# PROC099A_LC_Filtering_Reference.net
KiCad netlist of a schematic drawn in Altium Designer
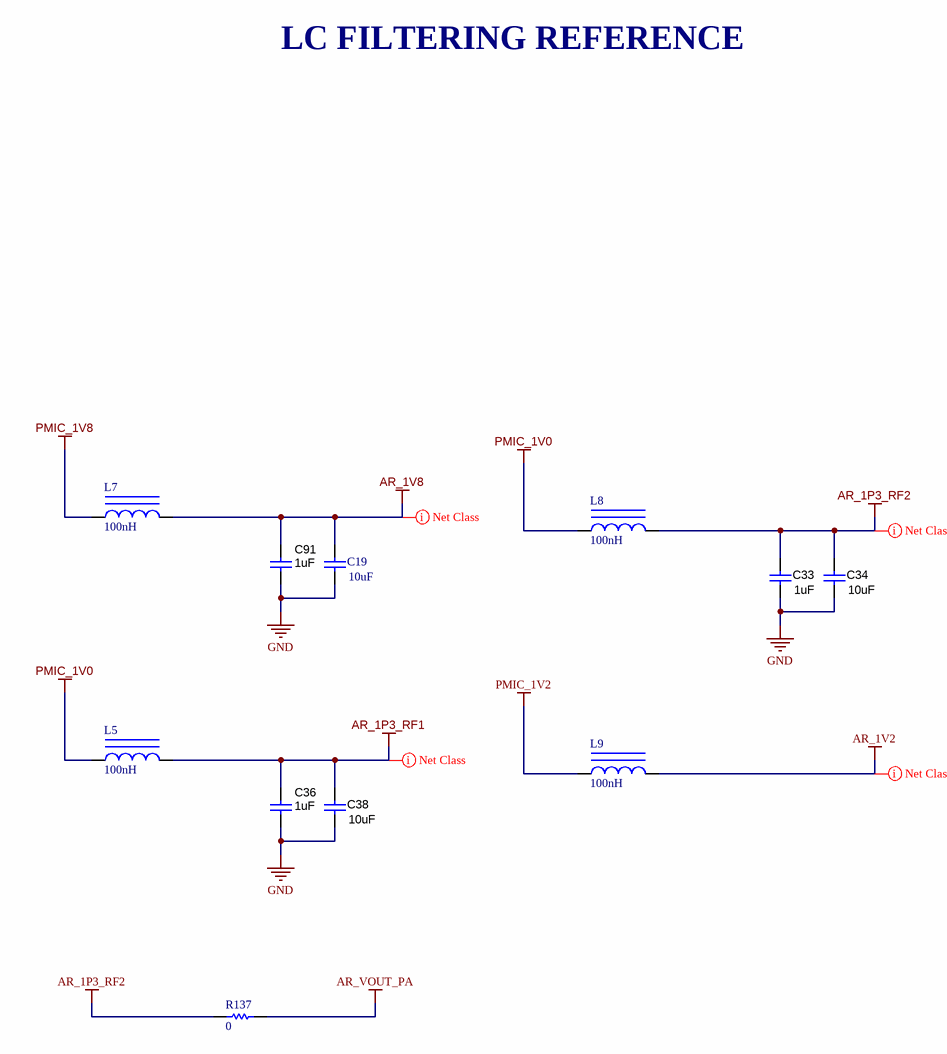
[diagram p0: PROC099A_LC_Filtering_Reference.SchDoc]

(export (version "E")
  (design (tool "Eeschema 10.0.6"))
  (components
    (comp (ref "C19")
      (value "GCM21BR71A106KE22L")
      (footprint "0805_HV")
      (description "CAP, CERM, 10 uF, 10 V, +/- 10%, X7R, 0805")
      (fields
        (field (name "MANUFACTURER") "MuRata")
        (field (name "VALUEDISPLAYED") "10uF")
        (field (name "PUBLISHER") "Texas Instruments")
      )
      (libsource (lib "Altium Vault - TI") (part "Capacitor"))
    )
    (comp (ref "C33")
      (value "GCM188R71C105KA64D")
      (footprint "0603")
      (description "CAP, CERM, 1 uF, 16 V, +/- 10%, X7R, AEC-Q200 Grade 1, 0603")
      (fields
        (field (name "MANUFACTURER") "MuRata")
        (field (name "VALUEDISPLAYED") "1uF")
        (field (name "PUBLISHER") "Texas Instruments")
      )
      (libsource (lib "Altium Vault - TI") (part "Capacitor"))
    )
    (comp (ref "C34")
      (value "GCM21BR71A106KE22L")
      (footprint "0805_HV")
      (description "CAP, CERM, 10 uF, 10 V, +/- 10%, X7R, 0805")
      (fields
        (field (name "MANUFACTURER") "MuRata")
        (field (name "VALUEDISPLAYED") "10uF")
        (field (name "PUBLISHER") "Texas Instruments")
      )
      (libsource (lib "Altium Vault - TI") (part "CMP-0008017-2"))
    )
    (comp (ref "C36")
      (value "GCM188R71C105KA64D")
      (footprint "0603")
      (description "CAP, CERM, 1 uF, 16 V, +/- 10%, X7R, AEC-Q200 Grade 1, 0603")
      (fields
        (field (name "MANUFACTURER") "MuRata")
        (field (name "VALUEDISPLAYED") "1uF")
        (field (name "PUBLISHER") "Texas Instruments")
      )
      (libsource (lib "Altium Vault - TI") (part "Capacitor"))
    )
    (comp (ref "C38")
      (value "GCM21BR71A106KE22L")
      (footprint "0805_HV")
      (description "CAP, CERM, 10 uF, 10 V, +/- 10%, X7R, 0805")
      (fields
        (field (name "MANUFACTURER") "MuRata")
        (field (name "VALUEDISPLAYED") "10uF")
        (field (name "PUBLISHER") "Texas Instruments")
      )
      (libsource (lib "Altium Vault - TI") (part "CMP-0008017-2"))
    )
    (comp (ref "C91")
      (value "GCM188R71C105KA64D")
      (footprint "0603")
      (description "CAP, CERM, 1 uF, 16 V, +/- 10%, X7R, AEC-Q200 Grade 1, 0603")
      (fields
        (field (name "MANUFACTURER") "MuRata")
        (field (name "VALUEDISPLAYED") "1uF")
        (field (name "PUBLISHER") "Texas Instruments")
      )
      (libsource (lib "Altium Vault - TI") (part "Capacitor"))
    )
    (comp (ref "L5")
      (value "NLCV32T-R10M-EFRD")
      (footprint "NLCV32")
      (description "Inductor, Wirewound, Ferrite, 100 nH, 2.85 A, 0.024 ohm, AEC-Q200 Grade 1, SMD")
      (fields (field (name "MANUFACTURER") "TDK") (field (name "VALUEDISPLAYED") "100nH"))
      (libsource (lib "Altium Vault - TI") (part "Inductor_Iron"))
    )
    (comp (ref "L7")
      (value "NLCV32T-R10M-EFRD")
      (footprint "NLCV32")
      (description "Inductor, Wirewound, Ferrite, 100 nH, 2.85 A, 0.024 ohm, AEC-Q200 Grade 1, SMD")
      (fields (field (name "MANUFACTURER") "TDK") (field (name "VALUEDISPLAYED") "100nH"))
      (libsource (lib "Altium Vault - TI") (part "Inductor_Iron"))
    )
    (comp (ref "L8")
      (value "NLCV32T-R10M-EFRD")
      (footprint "NLCV32")
      (description "Inductor, Wirewound, Ferrite, 100 nH, 2.85 A, 0.024 ohm, AEC-Q200 Grade 1, SMD")
      (fields (field (name "MANUFACTURER") "TDK") (field (name "VALUEDISPLAYED") "100nH"))
      (libsource (lib "Altium Vault - TI") (part "Inductor_Iron"))
    )
    (comp (ref "L9")
      (value "NLCV32T-R10M-EFRD")
      (footprint "NLCV32")
      (description "Inductor, Wirewound, Ferrite, 100 nH, 2.85 A, 0.024 ohm, AEC-Q200 Grade 1, SMD")
      (fields (field (name "MANUFACTURER") "TDK") (field (name "VALUEDISPLAYED") "100nH"))
      (libsource (lib "Altium Vault - TI") (part "Inductor_Iron"))
    )
    (comp (ref "R137")
      (value "MCT06030Z0000ZP500")
      (footprint "0603")
      (description "RES, 0, 5%, 0.125 W, 0603")
      (fields
        (field (name "MANUFACTURER") "Vishay/Beyschlag")
        (field (name "VALUEDISPLAYED") "0")
        (field (name "PUBLISHER") "Texas Instruments")
      )
      (libsource (lib "Altium Vault - TI") (part "CMP-0025884-3"))
    )
  )
  (nets
    (net (code "1") (name "AR_1P3_RF1") (class "Default")
      (node (ref "C36") (pin "2") (pinfunction "2_2") (pintype "passive"))
      (node (ref "C38") (pin "2") (pinfunction "2_2") (pintype "passive"))
      (node (ref "L5") (pin "2") (pinfunction "2_2") (pintype "passive"))
    )
    (net (code "2") (name "AR_1P3_RF2") (class "Default")
      (node (ref "C33") (pin "2") (pinfunction "2_2") (pintype "passive"))
      (node (ref "C34") (pin "2") (pinfunction "2_2") (pintype "passive"))
      (node (ref "L8") (pin "2") (pinfunction "2_2") (pintype "passive"))
      (node (ref "R137") (pin "1") (pinfunction "1_1") (pintype "passive"))
    )
    (net (code "3") (name "AR_1V2") (class "Default")
      (node (ref "L9") (pin "2") (pinfunction "2_2") (pintype "passive"))
    )
    (net (code "4") (name "AR_1V8") (class "Default")
      (node (ref "C19") (pin "1") (pinfunction "1_1") (pintype "passive"))
      (node (ref "C91") (pin "2") (pinfunction "2_2") (pintype "passive"))
      (node (ref "L7") (pin "2") (pinfunction "2_2") (pintype "passive"))
    )
    (net (code "5") (name "AR_VOUT_PA") (class "Default")
      (node (ref "R137") (pin "2") (pinfunction "2_2") (pintype "passive"))
    )
    (net (code "6") (name "GND") (class "Default")
      (node (ref "C19") (pin "2") (pinfunction "2_2") (pintype "passive"))
      (node (ref "C33") (pin "1") (pinfunction "1_1") (pintype "passive"))
      (node (ref "C34") (pin "1") (pinfunction "1_1") (pintype "passive"))
      (node (ref "C36") (pin "1") (pinfunction "1_1") (pintype "passive"))
      (node (ref "C38") (pin "1") (pinfunction "1_1") (pintype "passive"))
      (node (ref "C91") (pin "1") (pinfunction "1_1") (pintype "passive"))
    )
    (net (code "7") (name "PMIC_1V0") (class "Default")
      (node (ref "L5") (pin "1") (pinfunction "1_1") (pintype "passive"))
      (node (ref "L8") (pin "1") (pinfunction "1_1") (pintype "passive"))
    )
    (net (code "8") (name "PMIC_1V2") (class "Default")
      (node (ref "L9") (pin "1") (pinfunction "1_1") (pintype "passive"))
    )
    (net (code "9") (name "PMIC_1V8") (class "Default")
      (node (ref "L7") (pin "1") (pinfunction "1_1") (pintype "passive"))
    )
  )
)
